# opencanusb.net
KiCad netlist of a schematic drawn in EAGLE
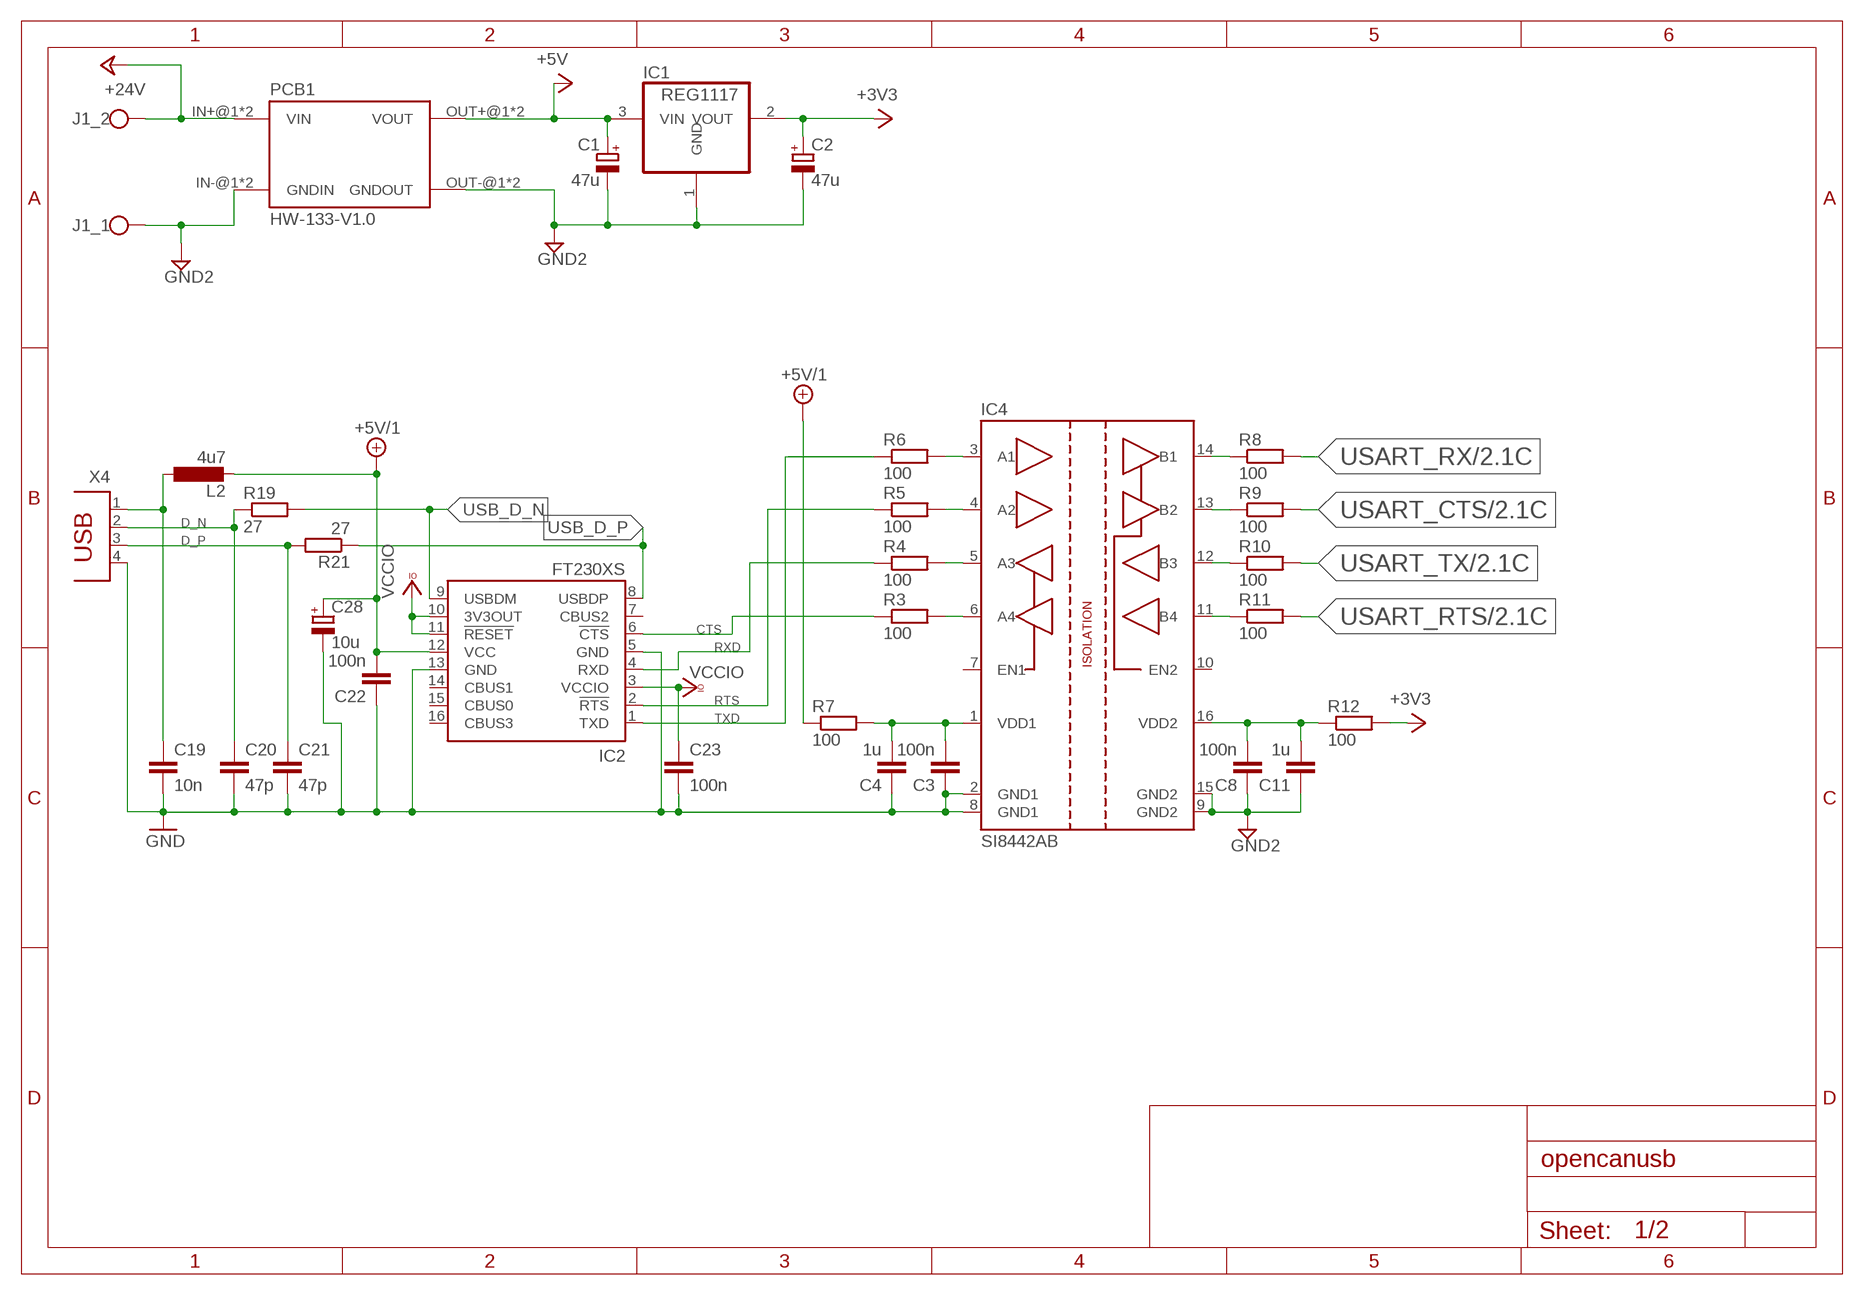
[diagram p0: schematic, sheet 1]
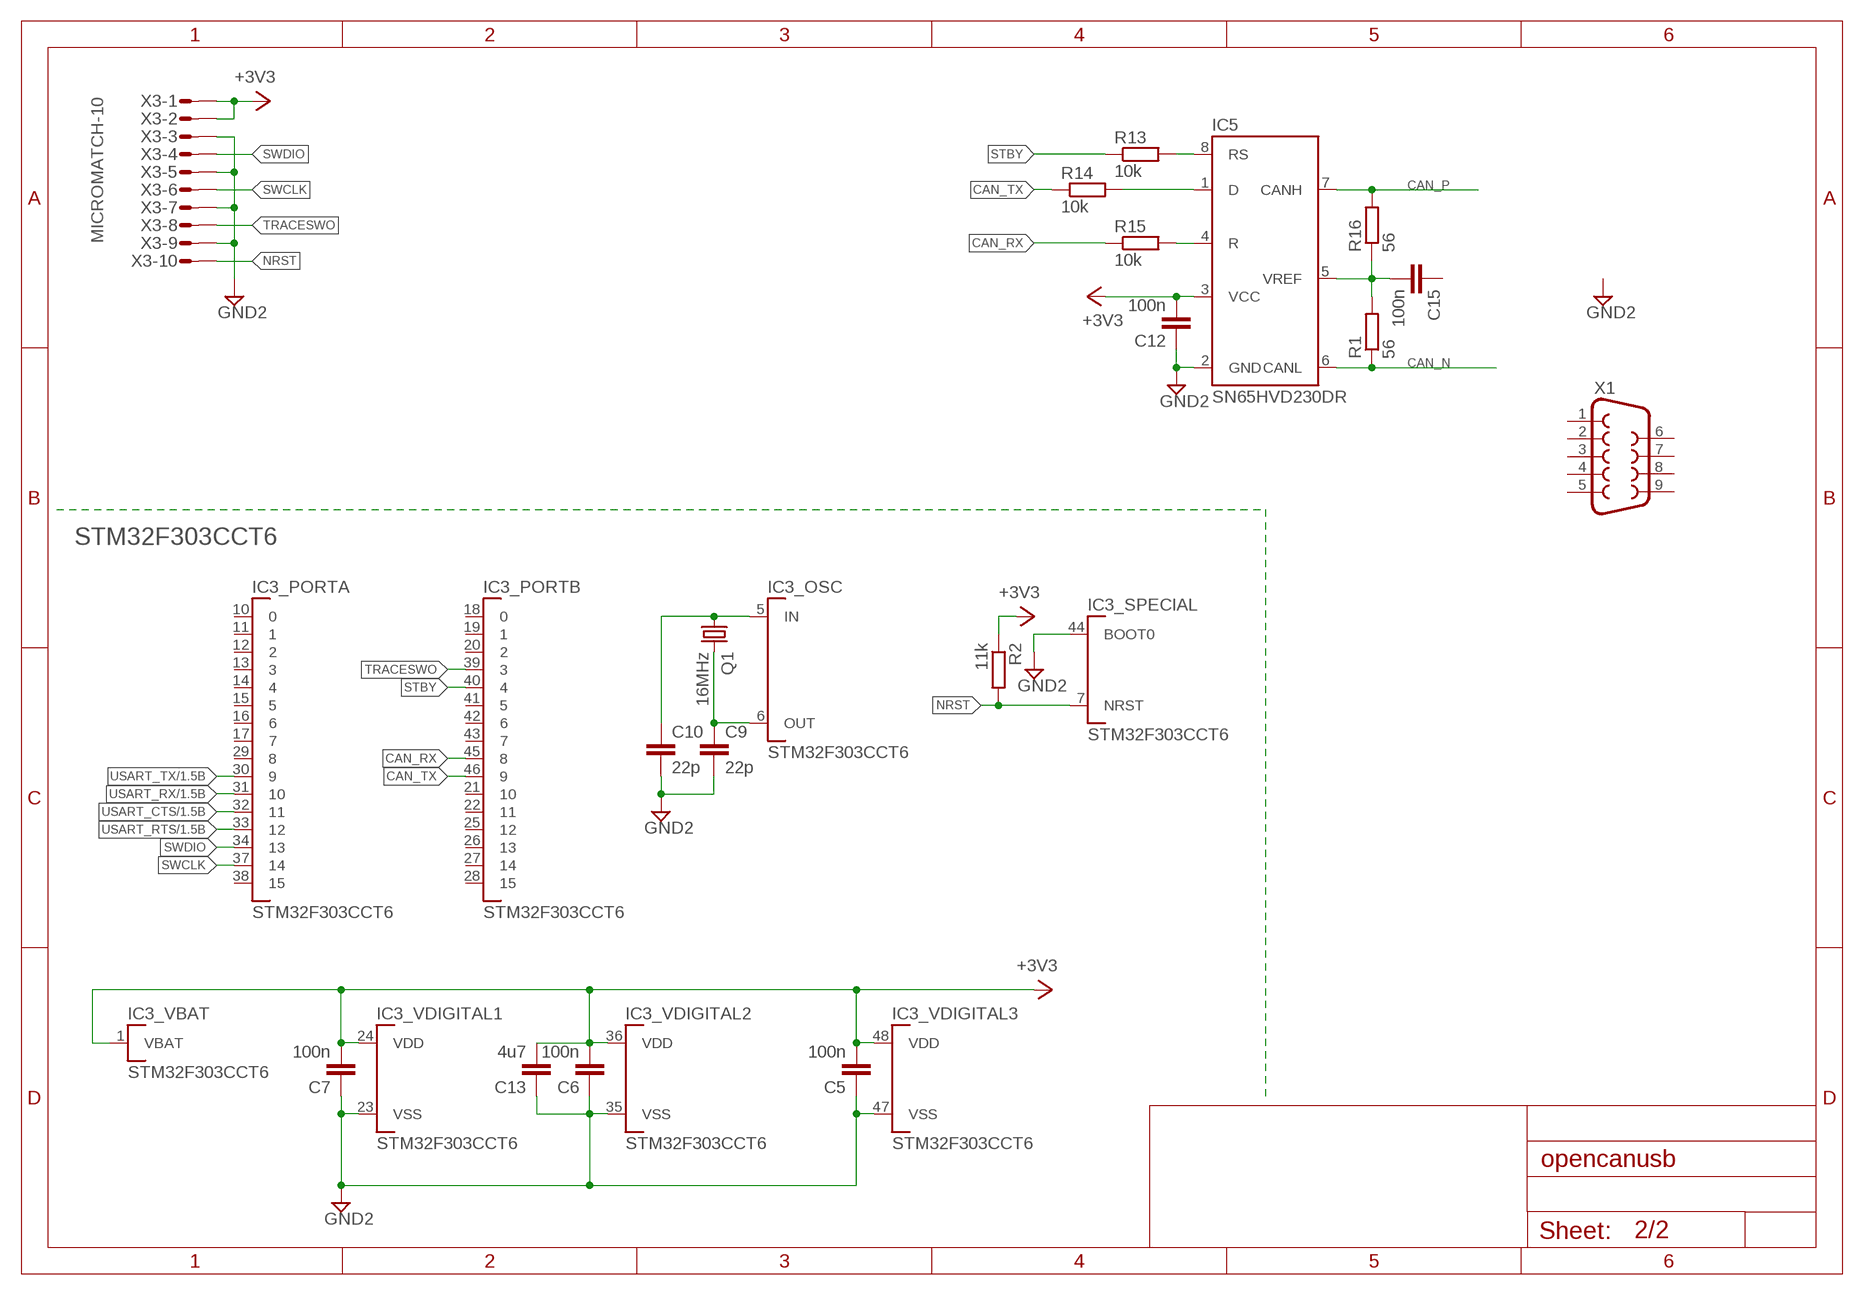
[diagram p1: schematic, sheet 2]

(export (version "E")
  (design (tool "Eeschema 10.0.6"))
  (components
    (comp (ref "C1")
      (value "47u")
      (footprint "eagle-import:E1,8-4")
      (libsource (lib "eagle-import") (part "CPOL-EUE1.8-4"))
    )
    (comp (ref "C2")
      (value "47u")
      (footprint "eagle-import:E1,8-4")
      (libsource (lib "eagle-import") (part "CPOL-EUE1.8-4"))
    )
    (comp (ref "C3")
      (value "100n")
      (footprint "eagle-import:C0805")
      (libsource (lib "eagle-import") (part "C-EUC0805"))
    )
    (comp (ref "C4")
      (value "1u")
      (footprint "eagle-import:C0805")
      (libsource (lib "eagle-import") (part "C-EUC0805"))
    )
    (comp (ref "C8")
      (value "100n")
      (footprint "eagle-import:C0805")
      (libsource (lib "eagle-import") (part "C-EUC0805"))
    )
    (comp (ref "C11")
      (value "1u")
      (footprint "eagle-import:C0805")
      (libsource (lib "eagle-import") (part "C-EUC0805"))
    )
    (comp (ref "C19")
      (value "10n")
      (footprint "eagle-import:C0402")
      (libsource (lib "eagle-import") (part "C-EUC0402"))
    )
    (comp (ref "C20")
      (value "47p")
      (footprint "eagle-import:C0603")
      (libsource (lib "eagle-import") (part "C-EUC0603"))
    )
    (comp (ref "C21")
      (value "47p")
      (footprint "eagle-import:C0603")
      (libsource (lib "eagle-import") (part "C-EUC0603"))
    )
    (comp (ref "C22")
      (value "100n")
      (footprint "eagle-import:C0805")
      (libsource (lib "eagle-import") (part "C-EUC0805"))
    )
    (comp (ref "C23")
      (value "100n")
      (footprint "eagle-import:C0805")
      (libsource (lib "eagle-import") (part "C-EUC0805"))
    )
    (comp (ref "C28")
      (value "10u")
      (footprint "eagle-import:SMC_A")
      (libsource (lib "eagle-import") (part "CPOL-EUSMCA"))
    )
    (comp (ref "IC1")
      (value "REG1117")
      (footprint "eagle-import:SOT223")
      (libsource (lib "eagle-import") (part "REG1117"))
    )
    (comp (ref "IC2")
      (value "FT230XS")
      (footprint "eagle-import:SSOP16")
      (libsource (lib "eagle-import") (part "FT230XS"))
    )
    (comp (ref "IC4")
      (value "SI8442AB")
      (footprint "eagle-import:SOIC127P1030X265-16N")
      (libsource (lib "eagle-import") (part "SI8442AB"))
    )
    (comp (ref "J1")
      (value "DG300-7.5")
      (footprint "eagle-import:DG300-7.5")
      (libsource (lib "eagle-import") (part "DG300-7.5"))
    )
    (comp (ref "L2")
      (value "4u7")
      (footprint "eagle-import:L1812")
      (libsource (lib "eagle-import") (part "L-EUL1812"))
    )
    (comp (ref "PCB1")
      (value "HW-133-V1.0")
      (footprint "eagle-import:HW-133")
      (libsource (lib "eagle-import") (part "HW-133-V1.0"))
    )
    (comp (ref "R3")
      (value "100")
      (footprint "eagle-import:R0603")
      (libsource (lib "eagle-import") (part "R-EU_R0603"))
    )
    (comp (ref "R4")
      (value "100")
      (footprint "eagle-import:R0603")
      (libsource (lib "eagle-import") (part "R-EU_R0603"))
    )
    (comp (ref "R5")
      (value "100")
      (footprint "eagle-import:R0603")
      (libsource (lib "eagle-import") (part "R-EU_R0603"))
    )
    (comp (ref "R6")
      (value "100")
      (footprint "eagle-import:R0603")
      (libsource (lib "eagle-import") (part "R-EU_R0603"))
    )
    (comp (ref "R7")
      (value "100")
      (footprint "eagle-import:R0603")
      (libsource (lib "eagle-import") (part "R-EU_R0603"))
    )
    (comp (ref "R8")
      (value "100")
      (footprint "eagle-import:R0603")
      (libsource (lib "eagle-import") (part "R-EU_R0603"))
    )
    (comp (ref "R9")
      (value "100")
      (footprint "eagle-import:R0603")
      (libsource (lib "eagle-import") (part "R-EU_R0603"))
    )
    (comp (ref "R10")
      (value "100")
      (footprint "eagle-import:R0603")
      (libsource (lib "eagle-import") (part "R-EU_R0603"))
    )
    (comp (ref "R11")
      (value "100")
      (footprint "eagle-import:R0603")
      (libsource (lib "eagle-import") (part "R-EU_R0603"))
    )
    (comp (ref "R12")
      (value "100")
      (footprint "eagle-import:R0603")
      (libsource (lib "eagle-import") (part "R-EU_R0603"))
    )
    (comp (ref "R19")
      (value "27")
      (footprint "eagle-import:R0805")
      (libsource (lib "eagle-import") (part "R-EU_R0805"))
    )
    (comp (ref "R21")
      (value "27")
      (footprint "eagle-import:R0805")
      (libsource (lib "eagle-import") (part "R-EU_R0805"))
    )
    (comp (ref "X4")
      (value "PN61729")
      (footprint "eagle-import:PN61729")
      (libsource (lib "eagle-import") (part "PN61729"))
    )
    (comp (ref "C5")
      (value "100n")
      (footprint "eagle-import:C0805")
      (libsource (lib "eagle-import") (part "C-EUC0805"))
    )
    (comp (ref "C6")
      (value "100n")
      (footprint "eagle-import:C0805")
      (libsource (lib "eagle-import") (part "C-EUC0805"))
    )
    (comp (ref "C7")
      (value "100n")
      (footprint "eagle-import:C0805")
      (libsource (lib "eagle-import") (part "C-EUC0805"))
    )
    (comp (ref "C9")
      (value "22p")
      (footprint "eagle-import:C0805")
      (libsource (lib "eagle-import") (part "C-EUC0805"))
    )
    (comp (ref "C10")
      (value "22p")
      (footprint "eagle-import:C0805")
      (libsource (lib "eagle-import") (part "C-EUC0805"))
    )
    (comp (ref "C12")
      (value "100n")
      (footprint "eagle-import:C0402")
      (libsource (lib "eagle-import") (part "C-EUC0402"))
    )
    (comp (ref "C13")
      (value "4u7")
      (footprint "eagle-import:C0805")
      (libsource (lib "eagle-import") (part "C-EUC0805"))
    )
    (comp (ref "C15")
      (value "100n")
      (footprint "eagle-import:C0805")
      (libsource (lib "eagle-import") (part "C-EUC0805"))
    )
    (comp (ref "IC3")
      (value "STM32F303CCT6")
      (footprint "eagle-import:QFP50P900X900X160-48N")
      (libsource (lib "eagle-import") (part "STM32F303CCT6"))
    )
    (comp (ref "IC5")
      (value "SN65HVD230DR")
      (footprint "eagle-import:SOIC127P599X175-8N")
      (libsource (lib "eagle-import") (part "SN65HVD230DR"))
    )
    (comp (ref "Q1")
      (value "16MHz")
      (footprint "eagle-import:HC49UP")
      (libsource (lib "eagle-import") (part "CRYSTALHC49UP"))
    )
    (comp (ref "R1")
      (value "56")
      (footprint "eagle-import:R1206")
      (libsource (lib "eagle-import") (part "R-EU_R1206"))
    )
    (comp (ref "R2")
      (value "11k")
      (footprint "eagle-import:R1206")
      (libsource (lib "eagle-import") (part "R-EU_R1206"))
    )
    (comp (ref "R13")
      (value "10k")
      (footprint "eagle-import:R1206")
      (libsource (lib "eagle-import") (part "R-EU_R1206"))
    )
    (comp (ref "R14")
      (value "10k")
      (footprint "eagle-import:R1206")
      (libsource (lib "eagle-import") (part "R-EU_R1206"))
    )
    (comp (ref "R15")
      (value "10k")
      (footprint "eagle-import:R1206")
      (libsource (lib "eagle-import") (part "R-EU_R1206"))
    )
    (comp (ref "R16")
      (value "56")
      (footprint "eagle-import:R1206")
      (libsource (lib "eagle-import") (part "R-EU_R1206"))
    )
    (comp (ref "X1")
      (value "F09HP")
      (footprint "eagle-import:F09HP")
      (libsource (lib "eagle-import") (part "F09HP"))
    )
    (comp (ref "X3")
      (value "MICROMATCH-10")
      (footprint "eagle-import:MICROMATCH-10")
      (fields (field (name "MF") "FARNELL") (field (name "MPN") "8-215464-0"))
      (libsource (lib "eagle-import") (part "MICROMATCH-10"))
    )
  )
  (nets
    (net (code "1") (name "+3V3") (class "Default")
      (node (ref "C12") (pin "2") (pinfunction "2_2") (pintype "passive"))
      (node (ref "C13") (pin "2") (pinfunction "2_2") (pintype "passive"))
      (node (ref "C2") (pin "+") (pinfunction "+_+") (pintype "passive"))
      (node (ref "C5") (pin "2") (pinfunction "2_2") (pintype "passive"))
      (node (ref "C6") (pin "2") (pinfunction "2_2") (pintype "passive"))
      (node (ref "C7") (pin "2") (pinfunction "2_2") (pintype "passive"))
      (node (ref "IC1") (pin "2") (pinfunction "VOUT_2") (pintype "output"))
      (node (ref "IC3") (pin "1") (pinfunction "VBAT_1") (pintype "power_in"))
      (node (ref "IC3") (pin "24") (pinfunction "VDD_24") (pintype "power_in"))
      (node (ref "IC3") (pin "36") (pinfunction "VDD_36") (pintype "power_in"))
      (node (ref "IC3") (pin "48") (pinfunction "VDD_48") (pintype "power_in"))
      (node (ref "IC5") (pin "3") (pinfunction "VCC_3") (pintype "power_in"))
      (node (ref "R12") (pin "2") (pinfunction "2_2") (pintype "passive"))
      (node (ref "R2") (pin "1") (pinfunction "1_1") (pintype "passive"))
      (node (ref "X3") (pin "1") (pinfunction "S_1") (pintype "passive"))
      (node (ref "X3") (pin "2") (pinfunction "S_2") (pintype "passive"))
    )
    (net (code "2") (name "+5V") (class "Default")
      (node (ref "C1") (pin "+") (pinfunction "+_+") (pintype "passive"))
      (node (ref "IC1") (pin "3") (pinfunction "VIN_3") (pintype "input"))
      (node (ref "PCB1") (pin "OUT+@1") (pinfunction "VOUT_OUT+@1") (pintype "power_in"))
      (node (ref "PCB1") (pin "OUT+@2") (pinfunction "VOUT_OUT+@2") (pintype "power_in"))
    )
    (net (code "3") (name "+5V{slash}1") (class "Default")
      (node (ref "C22") (pin "2") (pinfunction "2_2") (pintype "passive"))
      (node (ref "C28") (pin "+") (pinfunction "+_+") (pintype "passive"))
      (node (ref "IC2") (pin "12") (pinfunction "VCC_12") (pintype "power_in"))
      (node (ref "L2") (pin "2") (pinfunction "2_2") (pintype "passive"))
      (node (ref "R7") (pin "1") (pinfunction "1_1") (pintype "passive"))
    )
    (net (code "4") (name "+24V") (class "Default")
      (node (ref "J1") (pin "P$2") (pinfunction "KL_P$2") (pintype "passive"))
      (node (ref "PCB1") (pin "IN+@1") (pinfunction "VIN_IN+@1") (pintype "power_in"))
      (node (ref "PCB1") (pin "IN+@2") (pinfunction "VIN_IN+@2") (pintype "power_in"))
    )
    (net (code "5") (name "CAN_N") (class "Default")
      (node (ref "IC5") (pin "6") (pinfunction "CANL_6") (pintype "bidirectional"))
      (node (ref "R1") (pin "1") (pinfunction "1_1") (pintype "passive"))
    )
    (net (code "6") (name "CAN_P") (class "Default")
      (node (ref "IC5") (pin "7") (pinfunction "CANH_7") (pintype "bidirectional"))
      (node (ref "R16") (pin "2") (pinfunction "2_2") (pintype "passive"))
    )
    (net (code "7") (name "CAN_RX") (class "Default")
      (node (ref "IC3") (pin "45") (pinfunction "8_45") (pintype "bidirectional"))
      (node (ref "R15") (pin "1") (pinfunction "1_1") (pintype "passive"))
    )
    (net (code "8") (name "CAN_TX") (class "Default")
      (node (ref "IC3") (pin "46") (pinfunction "9_46") (pintype "bidirectional"))
      (node (ref "R14") (pin "1") (pinfunction "1_1") (pintype "passive"))
    )
    (net (code "9") (name "CTS") (class "Default")
      (node (ref "IC2") (pin "6") (pinfunction "~{CTS}_6") (pintype "input"))
      (node (ref "R3") (pin "1") (pinfunction "1_1") (pintype "passive"))
    )
    (net (code "10") (name "D_N") (class "Default")
      (node (ref "C20") (pin "1") (pinfunction "1_1") (pintype "passive"))
      (node (ref "R19") (pin "1") (pinfunction "1_1") (pintype "passive"))
      (node (ref "X4") (pin "2") (pinfunction "2_2") (pintype "passive"))
    )
    (net (code "11") (name "D_P") (class "Default")
      (node (ref "C21") (pin "1") (pinfunction "1_1") (pintype "passive"))
      (node (ref "R21") (pin "2") (pinfunction "2_2") (pintype "passive"))
      (node (ref "X4") (pin "3") (pinfunction "3_3") (pintype "passive"))
    )
    (net (code "12") (name "GND") (class "Default")
      (node (ref "C19") (pin "2") (pinfunction "2_2") (pintype "passive"))
      (node (ref "C20") (pin "2") (pinfunction "2_2") (pintype "passive"))
      (node (ref "C21") (pin "2") (pinfunction "2_2") (pintype "passive"))
      (node (ref "C22") (pin "1") (pinfunction "1_1") (pintype "passive"))
      (node (ref "C23") (pin "2") (pinfunction "2_2") (pintype "passive"))
      (node (ref "C28") (pin "-") (pinfunction "-_-") (pintype "passive"))
      (node (ref "C3") (pin "1") (pinfunction "1_1") (pintype "passive"))
      (node (ref "C4") (pin "1") (pinfunction "1_1") (pintype "passive"))
      (node (ref "IC2") (pin "13") (pinfunction "GND_13") (pintype "power_in"))
      (node (ref "IC2") (pin "5") (pinfunction "GND_5") (pintype "power_in"))
      (node (ref "IC4") (pin "2") (pinfunction "GND1_2") (pintype "power_in"))
      (node (ref "IC4") (pin "8") (pinfunction "GND1_8") (pintype "power_in"))
      (node (ref "X4") (pin "4") (pinfunction "4_4") (pintype "passive"))
    )
    (net (code "13") (name "GND2") (class "Default")
      (node (ref "C1") (pin "-") (pinfunction "-_-") (pintype "passive"))
      (node (ref "C10") (pin "2") (pinfunction "2_2") (pintype "passive"))
      (node (ref "C11") (pin "1") (pinfunction "1_1") (pintype "passive"))
      (node (ref "C12") (pin "1") (pinfunction "1_1") (pintype "passive"))
      (node (ref "C13") (pin "1") (pinfunction "1_1") (pintype "passive"))
      (node (ref "C2") (pin "-") (pinfunction "-_-") (pintype "passive"))
      (node (ref "C5") (pin "1") (pinfunction "1_1") (pintype "passive"))
      (node (ref "C6") (pin "1") (pinfunction "1_1") (pintype "passive"))
      (node (ref "C7") (pin "1") (pinfunction "1_1") (pintype "passive"))
      (node (ref "C8") (pin "1") (pinfunction "1_1") (pintype "passive"))
      (node (ref "C9") (pin "2") (pinfunction "2_2") (pintype "passive"))
      (node (ref "IC1") (pin "1") (pinfunction "GND_1") (pintype "power_in"))
      (node (ref "IC3") (pin "23") (pinfunction "VSS_23") (pintype "power_in"))
      (node (ref "IC3") (pin "35") (pinfunction "VSS_35") (pintype "power_in"))
      (node (ref "IC3") (pin "44") (pinfunction "BOOT0_44") (pintype "passive"))
      (node (ref "IC3") (pin "47") (pinfunction "VSS_47") (pintype "power_in"))
      (node (ref "IC4") (pin "15") (pinfunction "GND2_15") (pintype "power_in"))
      (node (ref "IC4") (pin "9") (pinfunction "GND2_9") (pintype "power_in"))
      (node (ref "IC5") (pin "2") (pinfunction "GND_2") (pintype "power_in"))
      (node (ref "J1") (pin "P$1") (pinfunction "KL_P$1") (pintype "passive"))
      (node (ref "PCB1") (pin "IN-@1") (pinfunction "GNDIN_IN-@1") (pintype "power_in"))
      (node (ref "PCB1") (pin "IN-@2") (pinfunction "GNDIN_IN-@2") (pintype "power_in"))
      (node (ref "PCB1") (pin "OUT-@1") (pinfunction "GNDOUT_OUT-@1") (pintype "power_in"))
      (node (ref "PCB1") (pin "OUT-@2") (pinfunction "GNDOUT_OUT-@2") (pintype "power_in"))
      (node (ref "X3") (pin "3") (pinfunction "S_3") (pintype "passive"))
      (node (ref "X3") (pin "5") (pinfunction "S_5") (pintype "passive"))
      (node (ref "X3") (pin "7") (pinfunction "S_7") (pintype "passive"))
      (node (ref "X3") (pin "9") (pinfunction "S_9") (pintype "passive"))
    )
    (net (code "14") (name "NRST") (class "Default")
      (node (ref "IC3") (pin "7") (pinfunction "NRST_7") (pintype "passive"))
      (node (ref "R2") (pin "2") (pinfunction "2_2") (pintype "passive"))
      (node (ref "X3") (pin "10") (pinfunction "S_10") (pintype "passive"))
    )
    (net (code "15") (name "Net-(C19-Pad1)") (class "Default")
      (node (ref "C19") (pin "1") (pinfunction "1_1") (pintype "passive"))
      (node (ref "L2") (pin "1") (pinfunction "1_1") (pintype "passive"))
      (node (ref "X4") (pin "1") (pinfunction "1_1") (pintype "passive"))
    )
    (net (code "16") (name "Net-(IC3A-IN)") (class "Default")
      (node (ref "C10") (pin "1") (pinfunction "1_1") (pintype "passive"))
      (node (ref "IC3") (pin "5") (pinfunction "IN_5") (pintype "passive"))
      (node (ref "Q1") (pin "1") (pinfunction "1_1") (pintype "passive"))
    )
    (net (code "17") (name "Net-(IC3A-OUT)") (class "Default")
      (node (ref "C9") (pin "1") (pinfunction "1_1") (pintype "passive"))
      (node (ref "IC3") (pin "6") (pinfunction "OUT_6") (pintype "passive"))
      (node (ref "Q1") (pin "2") (pinfunction "2_2") (pintype "passive"))
    )
    (net (code "18") (name "Net-(IC4-A1)") (class "Default")
      (node (ref "IC4") (pin "3") (pinfunction "A1_3") (pintype "output"))
      (node (ref "R6") (pin "2") (pinfunction "2_2") (pintype "passive"))
    )
    (net (code "19") (name "Net-(IC4-A2)") (class "Default")
      (node (ref "IC4") (pin "4") (pinfunction "A2_4") (pintype "output"))
      (node (ref "R5") (pin "2") (pinfunction "2_2") (pintype "passive"))
    )
    (net (code "20") (name "Net-(IC4-A3)") (class "Default")
      (node (ref "IC4") (pin "5") (pinfunction "A3_5") (pintype "input"))
      (node (ref "R4") (pin "2") (pinfunction "2_2") (pintype "passive"))
    )
    (net (code "21") (name "Net-(IC4-A4)") (class "Default")
      (node (ref "IC4") (pin "6") (pinfunction "A4_6") (pintype "input"))
      (node (ref "R3") (pin "2") (pinfunction "2_2") (pintype "passive"))
    )
    (net (code "22") (name "Net-(IC4-B1)") (class "Default")
      (node (ref "IC4") (pin "14") (pinfunction "B1_14") (pintype "output"))
      (node (ref "R8") (pin "1") (pinfunction "1_1") (pintype "passive"))
    )
    (net (code "23") (name "Net-(IC4-B2)") (class "Default")
      (node (ref "IC4") (pin "13") (pinfunction "B2_13") (pintype "output"))
      (node (ref "R9") (pin "1") (pinfunction "1_1") (pintype "passive"))
    )
    (net (code "24") (name "Net-(IC4-B3)") (class "Default")
      (node (ref "IC4") (pin "12") (pinfunction "B3_12") (pintype "input"))
      (node (ref "R10") (pin "1") (pinfunction "1_1") (pintype "passive"))
    )
    (net (code "25") (name "Net-(IC4-B4)") (class "Default")
      (node (ref "IC4") (pin "11") (pinfunction "B4_11") (pintype "input"))
      (node (ref "R11") (pin "1") (pinfunction "1_1") (pintype "passive"))
    )
    (net (code "26") (name "Net-(IC4-VDD1)") (class "Default")
      (node (ref "C3") (pin "2") (pinfunction "2_2") (pintype "passive"))
      (node (ref "C4") (pin "2") (pinfunction "2_2") (pintype "passive"))
      (node (ref "IC4") (pin "1") (pinfunction "VDD1_1") (pintype "power_in"))
      (node (ref "R7") (pin "2") (pinfunction "2_2") (pintype "passive"))
    )
    (net (code "27") (name "Net-(IC4-VDD2)") (class "Default")
      (node (ref "C11") (pin "2") (pinfunction "2_2") (pintype "passive"))
      (node (ref "C8") (pin "2") (pinfunction "2_2") (pintype "passive"))
      (node (ref "IC4") (pin "16") (pinfunction "VDD2_16") (pintype "power_in"))
      (node (ref "R12") (pin "1") (pinfunction "1_1") (pintype "passive"))
    )
    (net (code "28") (name "Net-(IC5-D)") (class "Default")
      (node (ref "IC5") (pin "1") (pinfunction "D_1") (pintype "input"))
      (node (ref "R14") (pin "2") (pinfunction "2_2") (pintype "passive"))
    )
    (net (code "29") (name "Net-(IC5-R)") (class "Default")
      (node (ref "IC5") (pin "4") (pinfunction "R_4") (pintype "output"))
      (node (ref "R15") (pin "2") (pinfunction "2_2") (pintype "passive"))
    )
    (net (code "30") (name "Net-(IC5-RS)") (class "Default")
      (node (ref "IC5") (pin "8") (pinfunction "RS_8") (pintype "power_in"))
      (node (ref "R13") (pin "2") (pinfunction "2_2") (pintype "passive"))
    )
    (net (code "31") (name "Net-(IC5-VREF)") (class "Default")
      (node (ref "C15") (pin "2") (pinfunction "2_2") (pintype "passive"))
      (node (ref "IC5") (pin "5") (pinfunction "VREF_5") (pintype "power_in"))
      (node (ref "R1") (pin "2") (pinfunction "2_2") (pintype "passive"))
      (node (ref "R16") (pin "1") (pinfunction "1_1") (pintype "passive"))
    )
    (net (code "32") (name "RTS") (class "Default")
      (node (ref "IC2") (pin "2") (pinfunction "~{RTS}_2") (pintype "output"))
      (node (ref "R5") (pin "1") (pinfunction "1_1") (pintype "passive"))
    )
    (net (code "33") (name "RXD") (class "Default")
      (node (ref "IC2") (pin "4") (pinfunction "RXD_4") (pintype "input"))
      (node (ref "R4") (pin "1") (pinfunction "1_1") (pintype "passive"))
    )
    (net (code "34") (name "STBY") (class "Default")
      (node (ref "IC3") (pin "40") (pinfunction "4_40") (pintype "bidirectional"))
      (node (ref "R13") (pin "1") (pinfunction "1_1") (pintype "passive"))
    )
    (net (code "35") (name "SWCLK") (class "Default")
      (node (ref "IC3") (pin "37") (pinfunction "14_37") (pintype "bidirectional"))
      (node (ref "X3") (pin "6") (pinfunction "S_6") (pintype "passive"))
    )
    (net (code "36") (name "SWDIO") (class "Default")
      (node (ref "IC3") (pin "34") (pinfunction "13_34") (pintype "bidirectional"))
      (node (ref "X3") (pin "4") (pinfunction "S_4") (pintype "passive"))
    )
    (net (code "37") (name "TRACESWO") (class "Default")
      (node (ref "IC3") (pin "39") (pinfunction "3_39") (pintype "bidirectional"))
      (node (ref "X3") (pin "8") (pinfunction "S_8") (pintype "passive"))
    )
    (net (code "38") (name "TXD") (class "Default")
      (node (ref "IC2") (pin "1") (pinfunction "TXD_1") (pintype "output"))
      (node (ref "R6") (pin "1") (pinfunction "1_1") (pintype "passive"))
    )
    (net (code "39") (name "USART_CTS") (class "Default")
      (node (ref "IC3") (pin "32") (pinfunction "11_32") (pintype "bidirectional"))
      (node (ref "R9") (pin "2") (pinfunction "2_2") (pintype "passive"))
    )
    (net (code "40") (name "USART_RTS") (class "Default")
      (node (ref "IC3") (pin "33") (pinfunction "12_33") (pintype "bidirectional"))
      (node (ref "R11") (pin "2") (pinfunction "2_2") (pintype "passive"))
    )
    (net (code "41") (name "USART_RX") (class "Default")
      (node (ref "IC3") (pin "31") (pinfunction "10_31") (pintype "bidirectional"))
      (node (ref "R8") (pin "2") (pinfunction "2_2") (pintype "passive"))
    )
    (net (code "42") (name "USART_TX") (class "Default")
      (node (ref "IC3") (pin "30") (pinfunction "9_30") (pintype "bidirectional"))
      (node (ref "R10") (pin "2") (pinfunction "2_2") (pintype "passive"))
    )
    (net (code "43") (name "USB_D_N") (class "Default")
      (node (ref "IC2") (pin "9") (pinfunction "USBDM_9") (pintype "input"))
      (node (ref "R19") (pin "2") (pinfunction "2_2") (pintype "passive"))
    )
    (net (code "44") (name "USB_D_P") (class "Default")
      (node (ref "IC2") (pin "8") (pinfunction "USBDP_8") (pintype "input"))
      (node (ref "R21") (pin "1") (pinfunction "1_1") (pintype "passive"))
    )
    (net (code "45") (name "VCCIO") (class "Default")
      (node (ref "C23") (pin "1") (pinfunction "1_1") (pintype "passive"))
      (node (ref "IC2") (pin "10") (pinfunction "3V3OUT_10") (pintype "output"))
      (node (ref "IC2") (pin "11") (pinfunction "~{RESET}_11") (pintype "input"))
      (node (ref "IC2") (pin "3") (pinfunction "VCCIO_3") (pintype "power_in"))
    )
    (net (code "46") (name "unconnected-(C15-Pad1)") (class "Default")
      (node (ref "C15") (pin "1") (pinfunction "1_1") (pintype "passive"))
    )
    (net (code "47") (name "unconnected-(IC2-CBUS0-Pad15)") (class "Default")
      (node (ref "IC2") (pin "15") (pinfunction "CBUS0_15") (pintype "bidirectional"))
    )
    (net (code "48") (name "unconnected-(IC2-CBUS1-Pad14)") (class "Default")
      (node (ref "IC2") (pin "14") (pinfunction "CBUS1_14") (pintype "bidirectional"))
    )
    (net (code "49") (name "unconnected-(IC2-CBUS2-Pad7)") (class "Default")
      (node (ref "IC2") (pin "7") (pinfunction "CBUS2_7") (pintype "bidirectional"))
    )
    (net (code "50") (name "unconnected-(IC2-CBUS3-Pad16)") (class "Default")
      (node (ref "IC2") (pin "16") (pinfunction "CBUS3_16") (pintype "bidirectional"))
    )
    (net (code "51") (name "unconnected-(IC3B-0-Pad10)") (class "Default")
      (node (ref "IC3") (pin "10") (pinfunction "0_10") (pintype "bidirectional"))
    )
    (net (code "52") (name "unconnected-(IC3B-1-Pad11)") (class "Default")
      (node (ref "IC3") (pin "11") (pinfunction "1_11") (pintype "bidirectional"))
    )
    (net (code "53") (name "unconnected-(IC3B-2-Pad12)") (class "Default")
      (node (ref "IC3") (pin "12") (pinfunction "2_12") (pintype "bidirectional"))
    )
    (net (code "54") (name "unconnected-(IC3B-3-Pad13)") (class "Default")
      (node (ref "IC3") (pin "13") (pinfunction "3_13") (pintype "bidirectional"))
    )
    (net (code "55") (name "unconnected-(IC3B-4-Pad14)") (class "Default")
      (node (ref "IC3") (pin "14") (pinfunction "4_14") (pintype "bidirectional"))
    )
    (net (code "56") (name "unconnected-(IC3B-5-Pad15)") (class "Default")
      (node (ref "IC3") (pin "15") (pinfunction "5_15") (pintype "bidirectional"))
    )
    (net (code "57") (name "unconnected-(IC3B-6-Pad16)") (class "Default")
      (node (ref "IC3") (pin "16") (pinfunction "6_16") (pintype "bidirectional"))
    )
    (net (code "58") (name "unconnected-(IC3B-7-Pad17)") (class "Default")
      (node (ref "IC3") (pin "17") (pinfunction "7_17") (pintype "bidirectional"))
    )
    (net (code "59") (name "unconnected-(IC3B-8-Pad29)") (class "Default")
      (node (ref "IC3") (pin "29") (pinfunction "8_29") (pintype "bidirectional"))
    )
    (net (code "60") (name "unconnected-(IC3B-15-Pad38)") (class "Default")
      (node (ref "IC3") (pin "38") (pinfunction "15_38") (pintype "bidirectional"))
    )
    (net (code "61") (name "unconnected-(IC3C-0-Pad18)") (class "Default")
      (node (ref "IC3") (pin "18") (pinfunction "0_18") (pintype "bidirectional"))
    )
    (net (code "62") (name "unconnected-(IC3C-1-Pad19)") (class "Default")
      (node (ref "IC3") (pin "19") (pinfunction "1_19") (pintype "bidirectional"))
    )
    (net (code "63") (name "unconnected-(IC3C-2-Pad20)") (class "Default")
      (node (ref "IC3") (pin "20") (pinfunction "2_20") (pintype "bidirectional"))
    )
    (net (code "64") (name "unconnected-(IC3C-5-Pad41)") (class "Default")
      (node (ref "IC3") (pin "41") (pinfunction "5_41") (pintype "bidirectional"))
    )
    (net (code "65") (name "unconnected-(IC3C-6-Pad42)") (class "Default")
      (node (ref "IC3") (pin "42") (pinfunction "6_42") (pintype "bidirectional"))
    )
    (net (code "66") (name "unconnected-(IC3C-7-Pad43)") (class "Default")
      (node (ref "IC3") (pin "43") (pinfunction "7_43") (pintype "bidirectional"))
    )
    (net (code "67") (name "unconnected-(IC3C-10-Pad21)") (class "Default")
      (node (ref "IC3") (pin "21") (pinfunction "10_21") (pintype "bidirectional"))
    )
    (net (code "68") (name "unconnected-(IC3C-11-Pad22)") (class "Default")
      (node (ref "IC3") (pin "22") (pinfunction "11_22") (pintype "bidirectional"))
    )
    (net (code "69") (name "unconnected-(IC3C-12-Pad25)") (class "Default")
      (node (ref "IC3") (pin "25") (pinfunction "12_25") (pintype "bidirectional"))
    )
    (net (code "70") (name "unconnected-(IC3C-13-Pad26)") (class "Default")
      (node (ref "IC3") (pin "26") (pinfunction "13_26") (pintype "bidirectional"))
    )
    (net (code "71") (name "unconnected-(IC3C-14-Pad27)") (class "Default")
      (node (ref "IC3") (pin "27") (pinfunction "14_27") (pintype "bidirectional"))
    )
    (net (code "72") (name "unconnected-(IC3C-15-Pad28)") (class "Default")
      (node (ref "IC3") (pin "28") (pinfunction "15_28") (pintype "bidirectional"))
    )
    (net (code "73") (name "unconnected-(IC4-EN1-Pad7)") (class "Default")
      (node (ref "IC4") (pin "7") (pinfunction "EN1_7") (pintype "input"))
    )
    (net (code "74") (name "unconnected-(IC4-EN2-Pad10)") (class "Default")
      (node (ref "IC4") (pin "10") (pinfunction "EN2_10") (pintype "input"))
    )
    (net (code "75") (name "unconnected-(X1-Pad1)") (class "Default")
      (node (ref "X1") (pin "1") (pinfunction "1_1") (pintype "passive"))
    )
    (net (code "76") (name "unconnected-(X1-Pad2)") (class "Default")
      (node (ref "X1") (pin "2") (pinfunction "2_2") (pintype "passive"))
    )
    (net (code "77") (name "unconnected-(X1-Pad3)") (class "Default")
      (node (ref "X1") (pin "3") (pinfunction "3_3") (pintype "passive"))
    )
    (net (code "78") (name "unconnected-(X1-Pad4)") (class "Default")
      (node (ref "X1") (pin "4") (pinfunction "4_4") (pintype "passive"))
    )
    (net (code "79") (name "unconnected-(X1-Pad5)") (class "Default")
      (node (ref "X1") (pin "5") (pinfunction "5_5") (pintype "passive"))
    )
    (net (code "80") (name "unconnected-(X1-Pad6)") (class "Default")
      (node (ref "X1") (pin "6") (pinfunction "6_6") (pintype "passive"))
    )
    (net (code "81") (name "unconnected-(X1-Pad7)") (class "Default")
      (node (ref "X1") (pin "7") (pinfunction "7_7") (pintype "passive"))
    )
    (net (code "82") (name "unconnected-(X1-Pad8)") (class "Default")
      (node (ref "X1") (pin "8") (pinfunction "8_8") (pintype "passive"))
    )
    (net (code "83") (name "unconnected-(X1-Pad9)") (class "Default")
      (node (ref "X1") (pin "9") (pinfunction "9_9") (pintype "passive"))
    )
  )
)
